# 03_LORA.net
KiCad netlist of a schematic drawn in Altium Designer
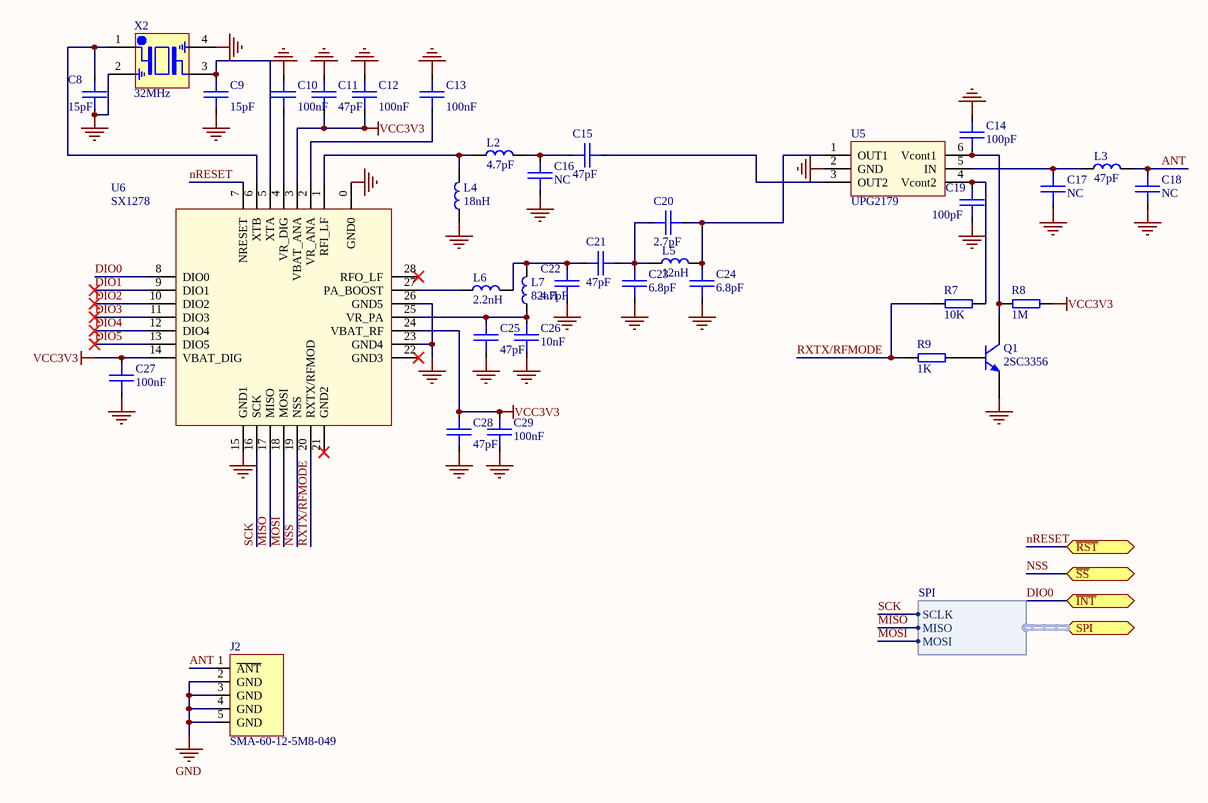
[diagram p0: 03_LORA.SchDoc]

(export (version "E")
  (design (tool "Eeschema 10.0.6"))
  (components
    (comp (ref "C8")
      (value "15pF")
      (footprint "SMT_C_0402")
      (description "Surface mount capacitor 0402")
      (libsource (lib "Vowstar_Basic_Device") (part "SMT_C_0402_1"))
    )
    (comp (ref "C9")
      (value "15pF")
      (footprint "SMT_C_0402")
      (description "Surface mount capacitor 0402")
      (libsource (lib "Vowstar_Basic_Device") (part "SMT_C_0402_1"))
    )
    (comp (ref "C10")
      (value "100nF")
      (footprint "SMT_C_0402")
      (description "Surface mount capacitor 0402")
      (libsource (lib "Vowstar_Basic_Device") (part "SMT_C_0402_1"))
    )
    (comp (ref "C11")
      (value "47pF")
      (footprint "SMT_C_0402")
      (description "Surface mount capacitor 0402")
      (libsource (lib "Vowstar_Basic_Device") (part "SMT_C_0402_1"))
    )
    (comp (ref "C12")
      (value "100nF")
      (footprint "SMT_C_0402")
      (description "Surface mount capacitor 0402")
      (libsource (lib "Vowstar_Basic_Device") (part "SMT_C_0402_1"))
    )
    (comp (ref "C13")
      (value "100nF")
      (footprint "SMT_C_0402")
      (description "Surface mount capacitor 0402")
      (libsource (lib "Vowstar_Basic_Device") (part "SMT_C_0402_1"))
    )
    (comp (ref "C14")
      (value "100pF")
      (footprint "SMT_C_0402")
      (description "Surface mount capacitor 0402")
      (libsource (lib "Vowstar_Basic_Device") (part "SMT_C_0402_1"))
    )
    (comp (ref "C15")
      (value "47pF")
      (footprint "SMT_C_0402")
      (description "Surface mount capacitor 0402")
      (libsource (lib "Vowstar_Basic_Device") (part "SMT_C_0402_1"))
    )
    (comp (ref "C16")
      (value "NC")
      (footprint "SMT_C_0402")
      (description "Surface mount capacitor 0402")
      (libsource (lib "Vowstar_Basic_Device") (part "SMT_C_0402_1"))
    )
    (comp (ref "C17")
      (value "NC")
      (footprint "SMT_C_0402")
      (description "Surface mount capacitor 0402")
      (libsource (lib "Vowstar_Basic_Device") (part "SMT_C_0402_1"))
    )
    (comp (ref "C18")
      (value "NC")
      (footprint "SMT_C_0402")
      (description "Surface mount capacitor 0402")
      (libsource (lib "Vowstar_Basic_Device") (part "SMT_C_0402_1"))
    )
    (comp (ref "C19")
      (value "100pF")
      (footprint "SMT_C_0402")
      (description "Surface mount capacitor 0402")
      (libsource (lib "Vowstar_Basic_Device") (part "SMT_C_0402_1"))
    )
    (comp (ref "C20")
      (value "2.7pF")
      (footprint "SMT_C_0402")
      (description "Surface mount capacitor 0402")
      (libsource (lib "Vowstar_Basic_Device") (part "SMT_C_0402_1"))
    )
    (comp (ref "C21")
      (value "47pF")
      (footprint "SMT_C_0402")
      (description "Surface mount capacitor 0402")
      (libsource (lib "Vowstar_Basic_Device") (part "SMT_C_0402_1"))
    )
    (comp (ref "C22")
      (value "4.7pF")
      (footprint "SMT_C_0402")
      (description "Surface mount capacitor 0402")
      (libsource (lib "Vowstar_Basic_Device") (part "SMT_C_0402_1"))
    )
    (comp (ref "C23")
      (value "6.8pF")
      (footprint "SMT_C_0402")
      (description "Surface mount capacitor 0402")
      (libsource (lib "Vowstar_Basic_Device") (part "SMT_C_0402_1"))
    )
    (comp (ref "C24")
      (value "6.8pF")
      (footprint "SMT_C_0402")
      (description "Surface mount capacitor 0402")
      (libsource (lib "Vowstar_Basic_Device") (part "SMT_C_0402_1"))
    )
    (comp (ref "C25")
      (value "47pF")
      (footprint "SMT_C_0402")
      (description "Surface mount capacitor 0402")
      (libsource (lib "Vowstar_Basic_Device") (part "SMT_C_0402_1"))
    )
    (comp (ref "C26")
      (value "10nF")
      (footprint "SMT_C_0402")
      (description "Surface mount capacitor 0402")
      (libsource (lib "Vowstar_Basic_Device") (part "SMT_C_0402_1"))
    )
    (comp (ref "C27")
      (value "100nF")
      (footprint "SMT_C_0402")
      (description "Surface mount capacitor 0402")
      (libsource (lib "Vowstar_Basic_Device") (part "SMT_C_0402_1"))
    )
    (comp (ref "C28")
      (value "47pF")
      (footprint "SMT_C_0402")
      (description "Surface mount capacitor 0402")
      (libsource (lib "Vowstar_Basic_Device") (part "SMT_C_0402_1"))
    )
    (comp (ref "C29")
      (value "100nF")
      (footprint "SMT_C_0402")
      (description "Surface mount capacitor 0402")
      (libsource (lib "Vowstar_Basic_Device") (part "SMT_C_0402_1"))
    )
    (comp (ref "J2")
      (value "SMA-60-12-5M8-049")
      (footprint "SMA-60-12-5M8-049")
      (description "sma 60-12-5M8-049")
      (libsource (lib "Vowstar_Connector") (part "SMA-60-12-5M8-049"))
    )
    (comp (ref "L2")
      (value "4.7pF")
      (footprint "SMT_L_0402")
      (description "Surface mount inductor 0402")
      (libsource (lib "Vowstar_Basic_Device") (part "SMT_L_0402"))
    )
    (comp (ref "L3")
      (value "47pF")
      (footprint "SMT_L_0402")
      (description "Surface mount inductor 0402")
      (libsource (lib "Vowstar_Basic_Device") (part "SMT_L_0402"))
    )
    (comp (ref "L4")
      (value "18nH")
      (footprint "SMT_L_0402")
      (description "Surface mount inductor 0402")
      (libsource (lib "Vowstar_Basic_Device") (part "SMT_L_0402"))
    )
    (comp (ref "L5")
      (value "12nH")
      (footprint "SMT_L_0402")
      (description "Surface mount inductor 0402")
      (libsource (lib "Vowstar_Basic_Device") (part "SMT_L_0402"))
    )
    (comp (ref "L6")
      (value "2.2nH")
      (footprint "SMT_L_0402")
      (description "Surface mount inductor 0402")
      (libsource (lib "Vowstar_Basic_Device") (part "SMT_L_0402"))
    )
    (comp (ref "L7")
      (value "82nH")
      (footprint "SMT_L_0402")
      (description "Surface mount inductor 0402")
      (libsource (lib "Vowstar_Basic_Device") (part "SMT_L_0402"))
    )
    (comp (ref "Q1")
      (value "2SC3356")
      (footprint "SOT-23S")
      (description "NPN Bipolar Transistor")
      (fields (field (name "PUBLISHER") "Altium Limited"))
      (libsource (lib "Schlib1") (part "NPN"))
    )
    (comp (ref "R7")
      (value "10K")
      (footprint "SMT_R_0402")
      (description "Surface mount resistor 0402")
      (libsource (lib "Vowstar_Basic_Device") (part "SMT_R_0402"))
    )
    (comp (ref "R8")
      (value "1M")
      (footprint "SMT_R_0402")
      (description "Surface mount resistor 0402")
      (libsource (lib "Vowstar_Basic_Device") (part "SMT_R_0402"))
    )
    (comp (ref "R9")
      (value "1K")
      (footprint "SMT_R_0402")
      (description "Surface mount resistor 0402")
      (libsource (lib "Vowstar_Basic_Device") (part "SMT_R_0402"))
    )
    (comp (ref "U5") (value "UPG2179") (footprint "SC70-6") (libsource (lib "Schlib1") (part "UPG2179")))
    (comp (ref "U6") (value "SX1278") (footprint "QFN28-6x6") (libsource (lib "Schlib1") (part "SX1278")))
    (comp (ref "X2")
      (value "32MHz")
      (footprint "SMT_XTAL_3225")
      (description "Passive crystal")
      (libsource (lib "Vowstar_Basic_Device") (part "SMT_XTAL_PASSIVE"))
    )
  )
  (nets
    (net (code "2") (name "/ANT") (class "Default")
      (node (ref "C18") (pin "2") (pinfunction "2_2") (pintype "passive"))
      (node (ref "J2") (pin "1") (pinfunction "~{ANT}_1") (pintype "passive"))
      (node (ref "L3") (pin "1") (pinfunction "1_1") (pintype "passive"))
    )
    (net (code "3") (name "/DIO0") (class "Default")
      (node (ref "U6") (pin "8") (pinfunction "DIO0_8") (pintype "passive"))
    )
    (net (code "4") (name "/DIO1") (class "Default")
      (node (ref "U6") (pin "9") (pinfunction "DIO1_9") (pintype "passive+no_connect"))
    )
    (net (code "5") (name "/DIO2") (class "Default")
      (node (ref "U6") (pin "10") (pinfunction "DIO2_10") (pintype "passive+no_connect"))
    )
    (net (code "6") (name "/DIO3") (class "Default")
      (node (ref "U6") (pin "11") (pinfunction "DIO3_11") (pintype "passive+no_connect"))
    )
    (net (code "7") (name "/DIO4") (class "Default")
      (node (ref "U6") (pin "12") (pinfunction "DIO4_12") (pintype "passive+no_connect"))
    )
    (net (code "8") (name "/DIO5") (class "Default")
      (node (ref "U6") (pin "13") (pinfunction "DIO5_13") (pintype "passive+no_connect"))
    )
    (net (code "9") (name "/MISO") (class "Default")
      (node (ref "U6") (pin "17") (pinfunction "MISO_17") (pintype "passive"))
    )
    (net (code "10") (name "/MOSI") (class "Default")
      (node (ref "U6") (pin "18") (pinfunction "MOSI_18") (pintype "passive"))
    )
    (net (code "11") (name "/NSS") (class "Default")
      (node (ref "U6") (pin "19") (pinfunction "NSS_19") (pintype "passive"))
    )
    (net (code "12") (name "/RXTX{slash}RFMODE") (class "Default")
      (node (ref "R7") (pin "1") (pinfunction "1_1") (pintype "passive"))
      (node (ref "R9") (pin "1") (pinfunction "1_1") (pintype "passive"))
      (node (ref "U6") (pin "20") (pinfunction "RXTX/RFMOD_20") (pintype "passive"))
    )
    (net (code "13") (name "/SCK") (class "Default")
      (node (ref "U6") (pin "16") (pinfunction "SCK_16") (pintype "passive"))
    )
    (net (code "14") (name "/nRESET") (class "Default")
      (node (ref "U6") (pin "7") (pinfunction "NRESET_7") (pintype "passive"))
    )
    (net (code "16") (name "GND") (class "Default")
      (node (ref "C10") (pin "2") (pinfunction "2_2") (pintype "passive"))
      (node (ref "C11") (pin "1") (pinfunction "1_1") (pintype "passive"))
      (node (ref "C12") (pin "2") (pinfunction "2_2") (pintype "passive"))
      (node (ref "C13") (pin "2") (pinfunction "2_2") (pintype "passive"))
      (node (ref "C14") (pin "2") (pinfunction "2_2") (pintype "passive"))
      (node (ref "C16") (pin "1") (pinfunction "1_1") (pintype "passive"))
      (node (ref "C17") (pin "1") (pinfunction "1_1") (pintype "passive"))
      (node (ref "C18") (pin "1") (pinfunction "1_1") (pintype "passive"))
      (node (ref "C19") (pin "1") (pinfunction "1_1") (pintype "passive"))
      (node (ref "C22") (pin "1") (pinfunction "1_1") (pintype "passive"))
      (node (ref "C23") (pin "1") (pinfunction "1_1") (pintype "passive"))
      (node (ref "C24") (pin "1") (pinfunction "1_1") (pintype "passive"))
      (node (ref "C25") (pin "1") (pinfunction "1_1") (pintype "passive"))
      (node (ref "C26") (pin "1") (pinfunction "1_1") (pintype "passive"))
      (node (ref "C27") (pin "2") (pinfunction "2_2") (pintype "passive"))
      (node (ref "C28") (pin "1") (pinfunction "1_1") (pintype "passive"))
      (node (ref "C29") (pin "1") (pinfunction "1_1") (pintype "passive"))
      (node (ref "C8") (pin "1") (pinfunction "1_1") (pintype "passive"))
      (node (ref "C9") (pin "1") (pinfunction "1_1") (pintype "passive"))
      (node (ref "J2") (pin "2") (pinfunction "GND_2") (pintype "passive"))
      (node (ref "J2") (pin "3") (pinfunction "GND_3") (pintype "passive"))
      (node (ref "J2") (pin "4") (pinfunction "GND_4") (pintype "passive"))
      (node (ref "J2") (pin "5") (pinfunction "GND_5") (pintype "passive"))
      (node (ref "L4") (pin "2") (pinfunction "2_2") (pintype "passive"))
      (node (ref "Q1") (pin "2") (pinfunction "E_2") (pintype "passive"))
      (node (ref "U5") (pin "2") (pinfunction "GND_2") (pintype "passive"))
      (node (ref "U6") (pin "0") (pinfunction "GND0_0") (pintype "passive"))
      (node (ref "U6") (pin "15") (pinfunction "GND1_15") (pintype "passive"))
      (node (ref "U6") (pin "23") (pinfunction "GND4_23") (pintype "passive"))
      (node (ref "U6") (pin "26") (pinfunction "GND5_26") (pintype "passive"))
      (node (ref "X2") (pin "2") (pinfunction "GND_2") (pintype "passive"))
      (node (ref "X2") (pin "4") (pinfunction "GND_4") (pintype "passive"))
    )
    (net (code "17") (name "Net-(C15-Pad2)") (class "Default")
      (node (ref "C15") (pin "2") (pinfunction "2_2") (pintype "passive"))
      (node (ref "C16") (pin "2") (pinfunction "2_2") (pintype "passive"))
      (node (ref "L2") (pin "1") (pinfunction "1_1") (pintype "passive"))
    )
    (net (code "18") (name "Net-(C20-Pad1)") (class "Default")
      (node (ref "C20") (pin "1") (pinfunction "1_1") (pintype "passive"))
      (node (ref "C21") (pin "2") (pinfunction "2_2") (pintype "passive"))
      (node (ref "C23") (pin "2") (pinfunction "2_2") (pintype "passive"))
      (node (ref "L5") (pin "2") (pinfunction "2_2") (pintype "passive"))
    )
    (net (code "19") (name "Net-(C21-Pad1)") (class "Default")
      (node (ref "C21") (pin "1") (pinfunction "1_1") (pintype "passive"))
      (node (ref "C22") (pin "2") (pinfunction "2_2") (pintype "passive"))
      (node (ref "L6") (pin "1") (pinfunction "1_1") (pintype "passive"))
      (node (ref "L7") (pin "1") (pinfunction "1_1") (pintype "passive"))
    )
    (net (code "20") (name "Net-(Q1-B)") (class "Default")
      (node (ref "Q1") (pin "1") (pinfunction "B_1") (pintype "passive"))
      (node (ref "R9") (pin "2") (pinfunction "2_2") (pintype "passive"))
    )
    (net (code "21") (name "Net-(Q1-C)") (class "Default")
      (node (ref "C14") (pin "1") (pinfunction "1_1") (pintype "passive"))
      (node (ref "Q1") (pin "3") (pinfunction "C_3") (pintype "passive"))
      (node (ref "R8") (pin "1") (pinfunction "1_1") (pintype "passive"))
      (node (ref "U5") (pin "6") (pinfunction "Vcont1_6") (pintype "passive"))
    )
    (net (code "22") (name "Net-(U5-IN)") (class "Default")
      (node (ref "C17") (pin "2") (pinfunction "2_2") (pintype "passive"))
      (node (ref "L3") (pin "2") (pinfunction "2_2") (pintype "passive"))
      (node (ref "U5") (pin "5") (pinfunction "IN_5") (pintype "passive"))
    )
    (net (code "23") (name "Net-(U5-OUT1)") (class "Default")
      (node (ref "C20") (pin "2") (pinfunction "2_2") (pintype "passive"))
      (node (ref "C24") (pin "2") (pinfunction "2_2") (pintype "passive"))
      (node (ref "L5") (pin "1") (pinfunction "1_1") (pintype "passive"))
      (node (ref "U5") (pin "1") (pinfunction "OUT1_1") (pintype "passive"))
    )
    (net (code "24") (name "Net-(U5-OUT2)") (class "Default")
      (node (ref "C15") (pin "1") (pinfunction "1_1") (pintype "passive"))
      (node (ref "U5") (pin "3") (pinfunction "OUT2_3") (pintype "passive"))
    )
    (net (code "25") (name "Net-(U5-Vcont2)") (class "Default")
      (node (ref "C19") (pin "2") (pinfunction "2_2") (pintype "passive"))
      (node (ref "R7") (pin "2") (pinfunction "2_2") (pintype "passive"))
      (node (ref "U5") (pin "4") (pinfunction "Vcont2_4") (pintype "passive"))
    )
    (net (code "26") (name "Net-(U6-PA_BOOST)") (class "Default")
      (node (ref "L6") (pin "2") (pinfunction "2_2") (pintype "passive"))
      (node (ref "U6") (pin "27") (pinfunction "PA_BOOST_27") (pintype "passive"))
    )
    (net (code "27") (name "Net-(U6-RFI_LF)") (class "Default")
      (node (ref "L2") (pin "2") (pinfunction "2_2") (pintype "passive"))
      (node (ref "L4") (pin "1") (pinfunction "1_1") (pintype "passive"))
      (node (ref "U6") (pin "1") (pinfunction "RFI_LF_1") (pintype "passive"))
    )
    (net (code "28") (name "Net-(U6-VR_ANA)") (class "Default")
      (node (ref "C13") (pin "1") (pinfunction "1_1") (pintype "passive"))
      (node (ref "U6") (pin "2") (pinfunction "VR_ANA_2") (pintype "passive"))
    )
    (net (code "29") (name "Net-(U6-VR_DIG)") (class "Default")
      (node (ref "C10") (pin "1") (pinfunction "1_1") (pintype "passive"))
      (node (ref "U6") (pin "4") (pinfunction "VR_DIG_4") (pintype "passive"))
    )
    (net (code "30") (name "Net-(U6-VR_PA)") (class "Default")
      (node (ref "C25") (pin "2") (pinfunction "2_2") (pintype "passive"))
      (node (ref "C26") (pin "2") (pinfunction "2_2") (pintype "passive"))
      (node (ref "L7") (pin "2") (pinfunction "2_2") (pintype "passive"))
      (node (ref "U6") (pin "25") (pinfunction "VR_PA_25") (pintype "passive"))
    )
    (net (code "31") (name "Net-(U6-XTA)") (class "Default")
      (node (ref "C9") (pin "2") (pinfunction "2_2") (pintype "passive"))
      (node (ref "U6") (pin "5") (pinfunction "XTA_5") (pintype "passive"))
      (node (ref "X2") (pin "3") (pinfunction "IN/OUT_3") (pintype "passive"))
    )
    (net (code "32") (name "Net-(U6-XTB)") (class "Default")
      (node (ref "C8") (pin "2") (pinfunction "2_2") (pintype "passive"))
      (node (ref "U6") (pin "6") (pinfunction "XTB_6") (pintype "passive"))
      (node (ref "X2") (pin "1") (pinfunction "IN/OUT_1") (pintype "passive"))
    )
    (net (code "33") (name "VCC3V3") (class "Default")
      (node (ref "C11") (pin "2") (pinfunction "2_2") (pintype "passive"))
      (node (ref "C12") (pin "1") (pinfunction "1_1") (pintype "passive"))
      (node (ref "C27") (pin "1") (pinfunction "1_1") (pintype "passive"))
      (node (ref "C28") (pin "2") (pinfunction "2_2") (pintype "passive"))
      (node (ref "C29") (pin "2") (pinfunction "2_2") (pintype "passive"))
      (node (ref "R8") (pin "2") (pinfunction "2_2") (pintype "passive"))
      (node (ref "U6") (pin "14") (pinfunction "VBAT_DIG_14") (pintype "passive"))
      (node (ref "U6") (pin "24") (pinfunction "VBAT_RF_24") (pintype "passive"))
      (node (ref "U6") (pin "3") (pinfunction "VBAT_ANA_3") (pintype "passive"))
    )
    (net (code "34") (name "unconnected-(U6-GND2-Pad21)") (class "Default")
      (node (ref "U6") (pin "21") (pinfunction "GND2_21") (pintype "passive+no_connect"))
    )
    (net (code "35") (name "unconnected-(U6-GND3-Pad22)") (class "Default")
      (node (ref "U6") (pin "22") (pinfunction "GND3_22") (pintype "passive+no_connect"))
    )
    (net (code "36") (name "unconnected-(U6-RFO_LF-Pad28)") (class "Default")
      (node (ref "U6") (pin "28") (pinfunction "RFO_LF_28") (pintype "passive+no_connect"))
    )
  )
)
